# trap_sensor_LD_schematic.net
KiCad netlist of a schematic drawn in Altium Designer
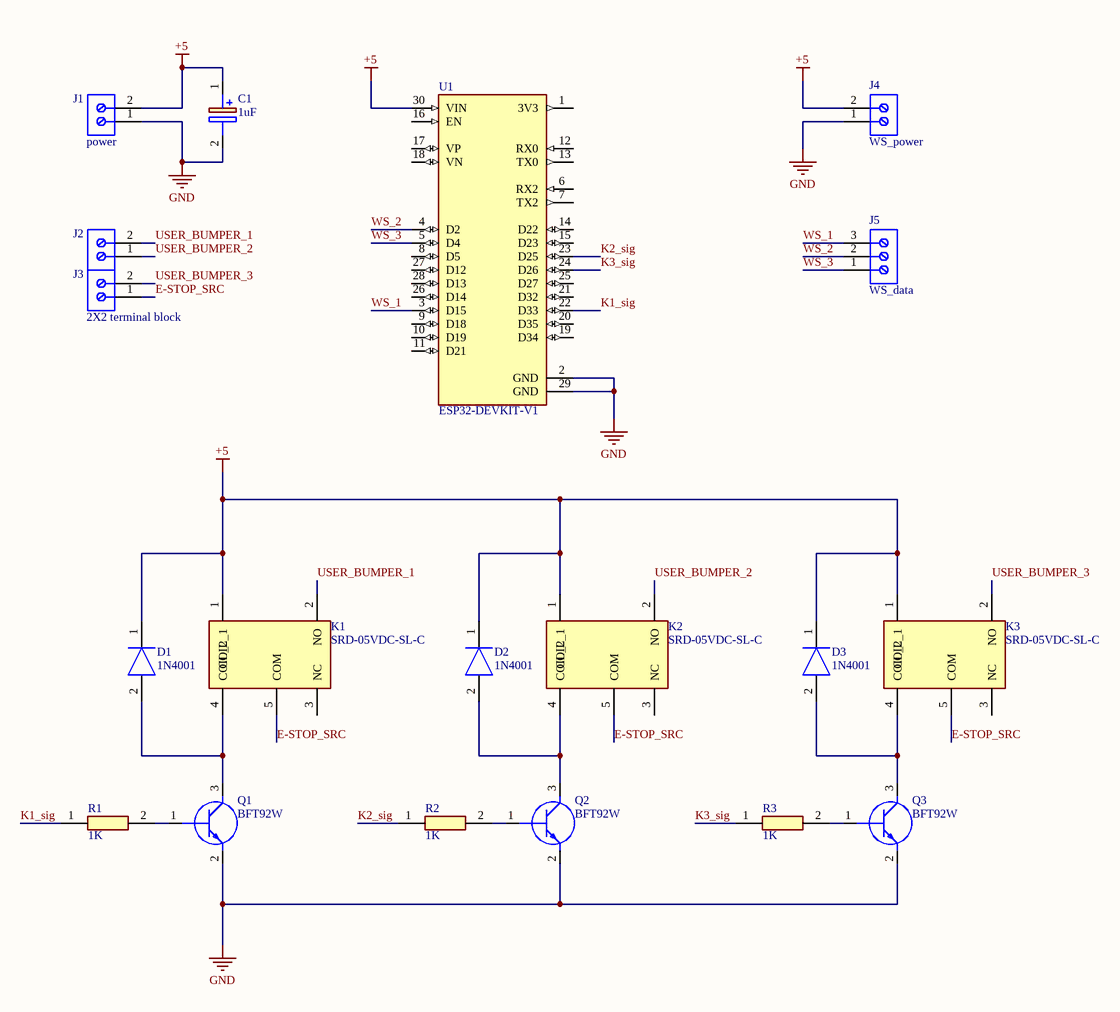
[diagram p0: trap sensor LD schematic.SchDoc]

(export (version "E")
  (design (tool "Eeschema 10.0.6"))
  (components
    (comp (ref "C1")
      (value "1uF")
      (footprint "CAPC3225X125N")
      (description "Capacitor Polarised")
      (fields
        (field (name "MANUFACTURER_PART_NUMBER") "MAL214699103E3")
        (field (name "MOUSER PART NUMBER") "594-MAL214699103E3")
      )
      (libsource (lib "SamacSys") (part "MAL214699103E3"))
    )
    (comp (ref "D1")
      (value "1N4001")
      (footprint "diode 2")
      (description "Diode")
      (fields (field (name "MOUSER PART NUMBER") "821-1N4001"))
      (libsource (lib "SamacSys") (part "1N4001"))
    )
    (comp (ref "D2")
      (value "1N4001")
      (footprint "diode 2")
      (description "Diode")
      (fields (field (name "MOUSER PART NUMBER") "821-1N4001"))
      (libsource (lib "SamacSys") (part "1N4001"))
    )
    (comp (ref "D3")
      (value "1N4001")
      (footprint "diode 2")
      (description "Diode")
      (fields (field (name "MOUSER PART NUMBER") "821-1N4001"))
      (libsource (lib "SamacSys") (part "1N4001"))
    )
    (comp (ref "J1")
      (value "power")
      (footprint "691102710002")
      (fields (field (name "VOLTAGE") "300V"))
      (libsource (lib "Altium Content Vault") (part "TBL - 1R - 02P - Screw"))
    )
    (comp (ref "J2")
      (value "~")
      (footprint "691102710002")
      (fields (field (name "VOLTAGE") "300V"))
      (libsource (lib "Altium Content Vault") (part "TBL - 1R - 02P - Screw"))
    )
    (comp (ref "J3")
      (value "2X2 terminal block")
      (footprint "691102710002")
      (fields (field (name "VOLTAGE") "300V"))
      (libsource (lib "Altium Content Vault") (part "TBL - 1R - 02P - Screw"))
    )
    (comp (ref "J4")
      (value "WS_power")
      (footprint "691102710002")
      (fields (field (name "VOLTAGE") "300V"))
      (libsource (lib "Altium Content Vault") (part "TBL - 1R - 02P - Screw"))
    )
    (comp (ref "J5")
      (value "WS_data")
      (footprint "691101710003")
      (fields (field (name "VOLTAGE") "250V"))
      (libsource (lib "Altium Content Vault") (part "TBL - 1R - 03P - Screw"))
    )
    (comp (ref "K1")
      (value "SRD-05VDC-SL-C")
      (footprint "SamacSys:SRD05VDCSLC")
      (description "Relay or Contactor")
      (libsource (lib "SamacSys") (part "SRD-05VDC-SL-C"))
    )
    (comp (ref "K2")
      (value "SRD-05VDC-SL-C")
      (footprint "SamacSys:SRD05VDCSLC")
      (description "Relay or Contactor")
      (libsource (lib "SamacSys") (part "SRD-05VDC-SL-C"))
    )
    (comp (ref "K3")
      (value "SRD-05VDC-SL-C")
      (footprint "SamacSys:SRD05VDCSLC")
      (description "Relay or Contactor")
      (libsource (lib "SamacSys") (part "SRD-05VDC-SL-C"))
    )
    (comp (ref "Q1")
      (value "BFT92W")
      (footprint "SamacSys:SOT65P210X110-3N")
      (description "Transistor BJT NPN")
      (libsource (lib "SamacSys") (part "BFT92W"))
    )
    (comp (ref "Q2")
      (value "BFT92W")
      (footprint "SamacSys:SOT65P210X110-3N")
      (description "Transistor BJT NPN")
      (libsource (lib "SamacSys") (part "BFT92W"))
    )
    (comp (ref "Q3")
      (value "BFT92W")
      (footprint "SamacSys:SOT65P210X110-3N")
      (description "Transistor BJT NPN")
      (libsource (lib "SamacSys") (part "BFT92W"))
    )
    (comp (ref "R1")
      (value "1K")
      (footprint "resistor smd")
      (description "Resistor")
      (fields
        (field (name "MANUFACTURER_PART_NUMBER") "MCU0805MD1001DP500")
        (field (name "MOUSER PART NUMBER") "594-MCU0805MD1001DP5")
      )
      (libsource (lib "SamacSys") (part "MCU0805MD1001DP500"))
    )
    (comp (ref "R2")
      (value "1K")
      (footprint "resistor smd")
      (description "Resistor")
      (fields
        (field (name "MANUFACTURER_PART_NUMBER") "MCU0805MD1001DP500")
        (field (name "MOUSER PART NUMBER") "594-MCU0805MD1001DP5")
      )
      (libsource (lib "SamacSys") (part "MCU0805MD1001DP500"))
    )
    (comp (ref "R3")
      (value "1K")
      (footprint "resistor smd")
      (description "Resistor")
      (fields
        (field (name "MANUFACTURER_PART_NUMBER") "MCU0805MD1001DP500")
        (field (name "MOUSER PART NUMBER") "594-MCU0805MD1001DP5")
      )
      (libsource (lib "SamacSys") (part "MCU0805MD1001DP500"))
    )
    (comp (ref "U1")
      (value "ESP32-DEVKIT-V1")
      (footprint "MODULE_ESP32_DEVKIT_V1")
      (fields (field (name "MF") "Do it"))
      (libsource (lib "SamacSys") (part "ESP32-DEVKIT-V1"))
    )
  )
  (nets
    (net (code "1") (name "+5") (class "Default")
      (node (ref "C1") (pin "1") (pinfunction "+_1") (pintype "passive"))
      (node (ref "D1") (pin "1") (pinfunction "K_1") (pintype "passive"))
      (node (ref "D2") (pin "1") (pinfunction "K_1") (pintype "passive"))
      (node (ref "D3") (pin "1") (pinfunction "K_1") (pintype "passive"))
      (node (ref "J1") (pin "2") (pinfunction "2_2") (pintype "passive"))
      (node (ref "J4") (pin "2") (pinfunction "2_2") (pintype "passive"))
      (node (ref "K1") (pin "1") (pinfunction "COIL_1_1") (pintype "passive"))
      (node (ref "K2") (pin "1") (pinfunction "COIL_1_1") (pintype "passive"))
      (node (ref "K3") (pin "1") (pinfunction "COIL_1_1") (pintype "passive"))
      (node (ref "U1") (pin "30") (pinfunction "VIN_30") (pintype "input"))
    )
    (net (code "2") (name "/E-STOP_SRC") (class "Default")
      (node (ref "J3") (pin "1") (pinfunction "1_1") (pintype "passive"))
      (node (ref "K1") (pin "5") (pinfunction "COM_5") (pintype "passive"))
      (node (ref "K2") (pin "5") (pinfunction "COM_5") (pintype "passive"))
      (node (ref "K3") (pin "5") (pinfunction "COM_5") (pintype "passive"))
    )
    (net (code "3") (name "/K1_sig") (class "Default")
      (node (ref "R1") (pin "1") (pinfunction "1_1") (pintype "passive"))
      (node (ref "U1") (pin "22") (pinfunction "D33_22") (pintype "bidirectional"))
    )
    (net (code "4") (name "/K2_sig") (class "Default")
      (node (ref "R2") (pin "1") (pinfunction "1_1") (pintype "passive"))
      (node (ref "U1") (pin "23") (pinfunction "D25_23") (pintype "bidirectional"))
    )
    (net (code "5") (name "/K3_sig") (class "Default")
      (node (ref "R3") (pin "1") (pinfunction "1_1") (pintype "passive"))
      (node (ref "U1") (pin "24") (pinfunction "D26_24") (pintype "bidirectional"))
    )
    (net (code "6") (name "/USER_BUMPER_1") (class "Default")
      (node (ref "J2") (pin "2") (pinfunction "2_2") (pintype "passive"))
      (node (ref "K1") (pin "2") (pinfunction "NO_2") (pintype "passive"))
    )
    (net (code "7") (name "/USER_BUMPER_2") (class "Default")
      (node (ref "J2") (pin "1") (pinfunction "1_1") (pintype "passive"))
      (node (ref "K2") (pin "2") (pinfunction "NO_2") (pintype "passive"))
    )
    (net (code "8") (name "/USER_BUMPER_3") (class "Default")
      (node (ref "J3") (pin "2") (pinfunction "2_2") (pintype "passive"))
      (node (ref "K3") (pin "2") (pinfunction "NO_2") (pintype "passive"))
    )
    (net (code "9") (name "/WS_1") (class "Default")
      (node (ref "J5") (pin "3") (pinfunction "3_3") (pintype "passive"))
      (node (ref "U1") (pin "3") (pinfunction "D15_3") (pintype "bidirectional"))
    )
    (net (code "10") (name "/WS_2") (class "Default")
      (node (ref "J5") (pin "2") (pinfunction "2_2") (pintype "passive"))
      (node (ref "U1") (pin "4") (pinfunction "D2_4") (pintype "bidirectional"))
    )
    (net (code "11") (name "/WS_3") (class "Default")
      (node (ref "J5") (pin "1") (pinfunction "1_1") (pintype "passive"))
      (node (ref "U1") (pin "5") (pinfunction "D4_5") (pintype "bidirectional"))
    )
    (net (code "12") (name "GND") (class "Default")
      (node (ref "C1") (pin "2") (pinfunction "-_2") (pintype "passive"))
      (node (ref "J1") (pin "1") (pinfunction "1_1") (pintype "passive"))
      (node (ref "J4") (pin "1") (pinfunction "1_1") (pintype "passive"))
      (node (ref "Q1") (pin "2") (pinfunction "E_2") (pintype "passive"))
      (node (ref "Q2") (pin "2") (pinfunction "E_2") (pintype "passive"))
      (node (ref "Q3") (pin "2") (pinfunction "E_2") (pintype "passive"))
      (node (ref "U1") (pin "2") (pinfunction "GND_2") (pintype "power_in"))
      (node (ref "U1") (pin "29") (pinfunction "GND_29") (pintype "power_in"))
    )
    (net (code "13") (name "Net-(D1-A)") (class "Default")
      (node (ref "D1") (pin "2") (pinfunction "A_2") (pintype "passive"))
      (node (ref "K1") (pin "4") (pinfunction "COIL_2_4") (pintype "passive"))
      (node (ref "Q1") (pin "3") (pinfunction "C_3") (pintype "passive"))
    )
    (net (code "14") (name "Net-(D2-A)") (class "Default")
      (node (ref "D2") (pin "2") (pinfunction "A_2") (pintype "passive"))
      (node (ref "K2") (pin "4") (pinfunction "COIL_2_4") (pintype "passive"))
      (node (ref "Q2") (pin "3") (pinfunction "C_3") (pintype "passive"))
    )
    (net (code "15") (name "Net-(D3-A)") (class "Default")
      (node (ref "D3") (pin "2") (pinfunction "A_2") (pintype "passive"))
      (node (ref "K3") (pin "4") (pinfunction "COIL_2_4") (pintype "passive"))
      (node (ref "Q3") (pin "3") (pinfunction "C_3") (pintype "passive"))
    )
    (net (code "16") (name "Net-(Q1-B)") (class "Default")
      (node (ref "Q1") (pin "1") (pinfunction "B_1") (pintype "passive"))
      (node (ref "R1") (pin "2") (pinfunction "2_2") (pintype "passive"))
    )
    (net (code "17") (name "Net-(Q2-B)") (class "Default")
      (node (ref "Q2") (pin "1") (pinfunction "B_1") (pintype "passive"))
      (node (ref "R2") (pin "2") (pinfunction "2_2") (pintype "passive"))
    )
    (net (code "18") (name "Net-(Q3-B)") (class "Default")
      (node (ref "Q3") (pin "1") (pinfunction "B_1") (pintype "passive"))
      (node (ref "R3") (pin "2") (pinfunction "2_2") (pintype "passive"))
    )
    (net (code "19") (name "unconnected-(K1-NC-Pad3)") (class "Default")
      (node (ref "K1") (pin "3") (pinfunction "NC_3") (pintype "passive"))
    )
    (net (code "20") (name "unconnected-(K2-NC-Pad3)") (class "Default")
      (node (ref "K2") (pin "3") (pinfunction "NC_3") (pintype "passive"))
    )
    (net (code "21") (name "unconnected-(K3-NC-Pad3)") (class "Default")
      (node (ref "K3") (pin "3") (pinfunction "NC_3") (pintype "passive"))
    )
    (net (code "22") (name "unconnected-(U1-3V3-Pad1)") (class "Default")
      (node (ref "U1") (pin "1") (pinfunction "3V3_1") (pintype "output"))
    )
    (net (code "23") (name "unconnected-(U1-D5-Pad8)") (class "Default")
      (node (ref "U1") (pin "8") (pinfunction "D5_8") (pintype "bidirectional"))
    )
    (net (code "24") (name "unconnected-(U1-D12-Pad27)") (class "Default")
      (node (ref "U1") (pin "27") (pinfunction "D12_27") (pintype "bidirectional"))
    )
    (net (code "25") (name "unconnected-(U1-D13-Pad28)") (class "Default")
      (node (ref "U1") (pin "28") (pinfunction "D13_28") (pintype "bidirectional"))
    )
    (net (code "26") (name "unconnected-(U1-D14-Pad26)") (class "Default")
      (node (ref "U1") (pin "26") (pinfunction "D14_26") (pintype "bidirectional"))
    )
    (net (code "27") (name "unconnected-(U1-D18-Pad9)") (class "Default")
      (node (ref "U1") (pin "9") (pinfunction "D18_9") (pintype "bidirectional"))
    )
    (net (code "28") (name "unconnected-(U1-D19-Pad10)") (class "Default")
      (node (ref "U1") (pin "10") (pinfunction "D19_10") (pintype "bidirectional"))
    )
    (net (code "29") (name "unconnected-(U1-D21-Pad11)") (class "Default")
      (node (ref "U1") (pin "11") (pinfunction "D21_11") (pintype "bidirectional"))
    )
    (net (code "30") (name "unconnected-(U1-D22-Pad14)") (class "Default")
      (node (ref "U1") (pin "14") (pinfunction "D22_14") (pintype "bidirectional"))
    )
    (net (code "31") (name "unconnected-(U1-D23-Pad15)") (class "Default")
      (node (ref "U1") (pin "15") (pinfunction "D23_15") (pintype "bidirectional"))
    )
    (net (code "32") (name "unconnected-(U1-D27-Pad25)") (class "Default")
      (node (ref "U1") (pin "25") (pinfunction "D27_25") (pintype "bidirectional"))
    )
    (net (code "33") (name "unconnected-(U1-D32-Pad21)") (class "Default")
      (node (ref "U1") (pin "21") (pinfunction "D32_21") (pintype "bidirectional"))
    )
    (net (code "34") (name "unconnected-(U1-D34-Pad19)") (class "Default")
      (node (ref "U1") (pin "19") (pinfunction "D34_19") (pintype "bidirectional"))
    )
    (net (code "35") (name "unconnected-(U1-D35-Pad20)") (class "Default")
      (node (ref "U1") (pin "20") (pinfunction "D35_20") (pintype "bidirectional"))
    )
    (net (code "36") (name "unconnected-(U1-EN-Pad16)") (class "Default")
      (node (ref "U1") (pin "16") (pinfunction "EN_16") (pintype "input"))
    )
    (net (code "37") (name "unconnected-(U1-RX0-Pad12)") (class "Default")
      (node (ref "U1") (pin "12") (pinfunction "RX0_12") (pintype "input"))
    )
    (net (code "38") (name "unconnected-(U1-RX2-Pad6)") (class "Default")
      (node (ref "U1") (pin "6") (pinfunction "RX2_6") (pintype "input"))
    )
    (net (code "39") (name "unconnected-(U1-TX0-Pad13)") (class "Default")
      (node (ref "U1") (pin "13") (pinfunction "TX0_13") (pintype "output"))
    )
    (net (code "40") (name "unconnected-(U1-TX2-Pad7)") (class "Default")
      (node (ref "U1") (pin "7") (pinfunction "TX2_7") (pintype "output"))
    )
    (net (code "41") (name "unconnected-(U1-VN-Pad18)") (class "Default")
      (node (ref "U1") (pin "18") (pinfunction "VN_18") (pintype "bidirectional"))
    )
    (net (code "42") (name "unconnected-(U1-VP-Pad17)") (class "Default")
      (node (ref "U1") (pin "17") (pinfunction "VP_17") (pintype "bidirectional"))
    )
  )
)
